# kiwi_23_usb_charger_v1_0.net
KiCad netlist of a schematic drawn in Altium Designer
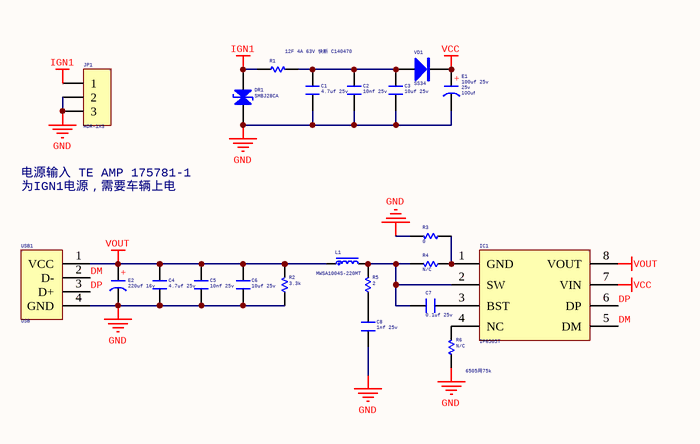
[diagram p0: kiwi_23_usb_charger_v1.0.schdoc]

(export (version "E")
  (design (tool "Eeschema 10.0.6"))
  (components
    (comp (ref "C1")
      (value "4.7uf 25v")
      (footprint "C 0805")
      (description "无极性贴片电容")
      (fields (field (name "VOLTAGE") "25v"))
      (libsource (lib "电阻-电容-电感") (part "C"))
    )
    (comp (ref "C2")
      (value "10nf 25v")
      (footprint "C 0805")
      (description "无极性贴片电容")
      (fields (field (name "VOLTAGE") "25v"))
      (libsource (lib "电阻-电容-电感") (part "C"))
    )
    (comp (ref "C3")
      (value "10uf 25v")
      (footprint "C 0805")
      (description "无极性贴片电容")
      (fields (field (name "VOLTAGE") "25v"))
      (libsource (lib "电阻-电容-电感") (part "C"))
    )
    (comp (ref "C4")
      (value "4.7uf 25v")
      (footprint "C 0805")
      (description "无极性贴片电容")
      (fields (field (name "VOLTAGE") "25v"))
      (libsource (lib "电阻-电容-电感") (part "C"))
    )
    (comp (ref "C5")
      (value "10nf 25v")
      (footprint "C 0805")
      (description "无极性贴片电容")
      (fields (field (name "VOLTAGE") "25v"))
      (libsource (lib "电阻-电容-电感") (part "C"))
    )
    (comp (ref "C6")
      (value "10uf 25v")
      (footprint "C 0805")
      (description "无极性贴片电容")
      (fields (field (name "VOLTAGE") "25v"))
      (libsource (lib "电阻-电容-电感") (part "C"))
    )
    (comp (ref "C7")
      (value "0.1uf 25v")
      (footprint "C 0603")
      (description "无极性贴片电容")
      (fields (field (name "VOLTAGE") "25v"))
      (libsource (lib "电阻-电容-电感") (part "C"))
    )
    (comp (ref "C8")
      (value "1nf 25v")
      (footprint "C 0603")
      (description "无极性贴片电容")
      (fields (field (name "VOLTAGE") "25v"))
      (libsource (lib "电阻-电容-电感") (part "C"))
    )
    (comp (ref "DR1")
      (value "SMBJ28CA")
      (footprint "SMB")
      (description "瞬态电压抑制二极管")
      (libsource (lib "二极管-整流桥") (part "DR"))
    )
    (comp (ref "E1")
      (value "100uf 25v")
      (footprint "CM D(6.3*7.7)")
      (description "贴片电解电容")
      (fields (field (name "VOLTAGE") "25v") (field (name "ALTIUM_VALUE") "100uf"))
      (libsource (lib "电阻-电容-电感") (part "C-CM"))
    )
    (comp (ref "E2")
      (value "220uf 16v")
      (footprint "CM D(6.3*7.7)")
      (description "贴片电解电容")
      (fields (field (name "VOLTAGE") "16v"))
      (libsource (lib "电阻-电容-电感") (part "C-CM"))
    )
    (comp (ref "IC1")
      (value "IP6505T")
      (footprint "SOP8_EPAD_L")
      (description "DCP/QC2.0/QC3.0/MTK PE1.1/PE2.0/FCP/SCP/AFC/SFCP 单A口降压模式快充管理器")
      (libsource (lib "IC芯片") (part "IP6505T"))
    )
    (comp (ref "JP1")
      (value "HDR-1X3")
      (footprint "TE AMP 175781-1-ND")
      (description "3P接插件")
      (libsource (lib "接插件") (part "Header 3"))
    )
    (comp (ref "L1")
      (value "MWSA1004S-220MT")
      (footprint "IND-SMD_L11.5-W10.0_FXL1040")
      (description "功率屏蔽电感")
      (libsource (lib "电阻-电容-电感") (part "L-CDRH"))
    )
    (comp (ref "R1")
      (value "12F 4A 63V 快断 C140470")
      (footprint "R 1206-HP")
      (description "贴片电阻")
      (libsource (lib "电阻-电容-电感") (part "R"))
    )
    (comp (ref "R2")
      (value "3.3k")
      (footprint "R 0603")
      (description "贴片电阻")
      (libsource (lib "电阻-电容-电感") (part "R"))
    )
    (comp (ref "R3")
      (value "0")
      (footprint "R 0603")
      (description "贴片电阻")
      (libsource (lib "电阻-电容-电感") (part "R"))
    )
    (comp (ref "R4")
      (value "N/C")
      (footprint "R 0603")
      (description "贴片电阻")
      (libsource (lib "电阻-电容-电感") (part "R"))
    )
    (comp (ref "R5")
      (value "2")
      (footprint "R 0603")
      (description "贴片电阻")
      (libsource (lib "电阻-电容-电感") (part "R"))
    )
    (comp (ref "R6")
      (value "N/C")
      (footprint "R 0603")
      (description "贴片电阻")
      (libsource (lib "电阻-电容-电感") (part "R"))
    )
    (comp (ref "USB1")
      (value "USB")
      (footprint "USB-A/S_A")
      (description "USB-A型母接口")
      (libsource (lib "接口类") (part "USB-A/S"))
    )
    (comp (ref "VD1")
      (value "SS34")
      (footprint "SMB")
      (description "肖特基二极管")
      (libsource (lib "二极管-整流桥") (part "SS34"))
    )
  )
  (nets
    (net (code "1") (name "/DM") (class "Default")
      (node (ref "IC1") (pin "5") (pinfunction "DM_5") (pintype "passive"))
      (node (ref "USB1") (pin "2") (pinfunction "D-_2") (pintype "passive"))
    )
    (net (code "2") (name "/DP") (class "Default")
      (node (ref "IC1") (pin "6") (pinfunction "DP_6") (pintype "passive"))
      (node (ref "USB1") (pin "3") (pinfunction "D+_3") (pintype "passive"))
    )
    (net (code "3") (name "GND") (class "Default")
      (node (ref "C1") (pin "1") (pinfunction "1_1") (pintype "passive"))
      (node (ref "C2") (pin "1") (pinfunction "1_1") (pintype "passive"))
      (node (ref "C3") (pin "1") (pinfunction "1_1") (pintype "passive"))
      (node (ref "C4") (pin "1") (pinfunction "1_1") (pintype "passive"))
      (node (ref "C5") (pin "1") (pinfunction "1_1") (pintype "passive"))
      (node (ref "C6") (pin "1") (pinfunction "1_1") (pintype "passive"))
      (node (ref "C8") (pin "2") (pinfunction "2_2") (pintype "passive"))
      (node (ref "DR1") (pin "2") (pinfunction "K_2") (pintype "passive"))
      (node (ref "E1") (pin "2") (pinfunction "2_2") (pintype "passive"))
      (node (ref "E2") (pin "2") (pinfunction "2_2") (pintype "passive"))
      (node (ref "JP1") (pin "2") (pinfunction "2_2") (pintype "passive"))
      (node (ref "JP1") (pin "3") (pinfunction "3_3") (pintype "passive"))
      (node (ref "R2") (pin "1") (pinfunction "1_1") (pintype "passive"))
      (node (ref "R3") (pin "2") (pinfunction "2_2") (pintype "passive"))
      (node (ref "R6") (pin "1") (pinfunction "1_1") (pintype "passive"))
      (node (ref "USB1") (pin "4") (pinfunction "GND_4") (pintype "passive"))
    )
    (net (code "4") (name "IGN1") (class "Default")
      (node (ref "DR1") (pin "1") (pinfunction "A_1") (pintype "passive"))
      (node (ref "JP1") (pin "1") (pinfunction "1_1") (pintype "passive"))
      (node (ref "R1") (pin "1") (pinfunction "1_1") (pintype "passive"))
    )
    (net (code "5") (name "Net-(C8-Pad1)") (class "Default")
      (node (ref "C8") (pin "1") (pinfunction "1_1") (pintype "passive"))
      (node (ref "R5") (pin "1") (pinfunction "1_1") (pintype "passive"))
    )
    (net (code "6") (name "Net-(IC1-BST)") (class "Default")
      (node (ref "C7") (pin "1") (pinfunction "1_1") (pintype "passive"))
      (node (ref "IC1") (pin "3") (pinfunction "BST_3") (pintype "passive"))
    )
    (net (code "7") (name "Net-(IC1-GND)") (class "Default")
      (node (ref "IC1") (pin "1") (pinfunction "GND_1") (pintype "passive"))
      (node (ref "R3") (pin "1") (pinfunction "1_1") (pintype "passive"))
      (node (ref "R4") (pin "1") (pinfunction "1_1") (pintype "passive"))
    )
    (net (code "8") (name "Net-(IC1-NC)") (class "Default")
      (node (ref "IC1") (pin "4") (pinfunction "NC_4") (pintype "passive"))
      (node (ref "R6") (pin "2") (pinfunction "2_2") (pintype "passive"))
    )
    (net (code "9") (name "Net-(IC1-SW)") (class "Default")
      (node (ref "C7") (pin "2") (pinfunction "2_2") (pintype "passive"))
      (node (ref "IC1") (pin "2") (pinfunction "SW_2") (pintype "passive"))
      (node (ref "L1") (pin "2") (pinfunction "2_2") (pintype "passive"))
      (node (ref "R4") (pin "2") (pinfunction "2_2") (pintype "passive"))
      (node (ref "R5") (pin "2") (pinfunction "2_2") (pintype "passive"))
    )
    (net (code "10") (name "Net-(VD1-A)") (class "Default")
      (node (ref "C1") (pin "2") (pinfunction "2_2") (pintype "passive"))
      (node (ref "C2") (pin "2") (pinfunction "2_2") (pintype "passive"))
      (node (ref "C3") (pin "2") (pinfunction "2_2") (pintype "passive"))
      (node (ref "R1") (pin "2") (pinfunction "2_2") (pintype "passive"))
      (node (ref "VD1") (pin "1") (pinfunction "A_1") (pintype "passive"))
    )
    (net (code "11") (name "VCC") (class "Default")
      (node (ref "E1") (pin "1") (pinfunction "1_1") (pintype "passive"))
      (node (ref "IC1") (pin "7") (pinfunction "VIN_7") (pintype "passive"))
      (node (ref "VD1") (pin "2") (pinfunction "K_2") (pintype "passive"))
    )
    (net (code "12") (name "VOUT") (class "Default")
      (node (ref "C4") (pin "2") (pinfunction "2_2") (pintype "passive"))
      (node (ref "C5") (pin "2") (pinfunction "2_2") (pintype "passive"))
      (node (ref "C6") (pin "2") (pinfunction "2_2") (pintype "passive"))
      (node (ref "E2") (pin "1") (pinfunction "1_1") (pintype "passive"))
      (node (ref "IC1") (pin "8") (pinfunction "VOUT_8") (pintype "passive"))
      (node (ref "L1") (pin "1") (pinfunction "1_1") (pintype "passive"))
      (node (ref "R2") (pin "2") (pinfunction "2_2") (pintype "passive"))
      (node (ref "USB1") (pin "1") (pinfunction "VCC_1") (pintype "passive"))
    )
  )
)
